# electrovanne.net
KiCad netlist of a schematic drawn in EAGLE
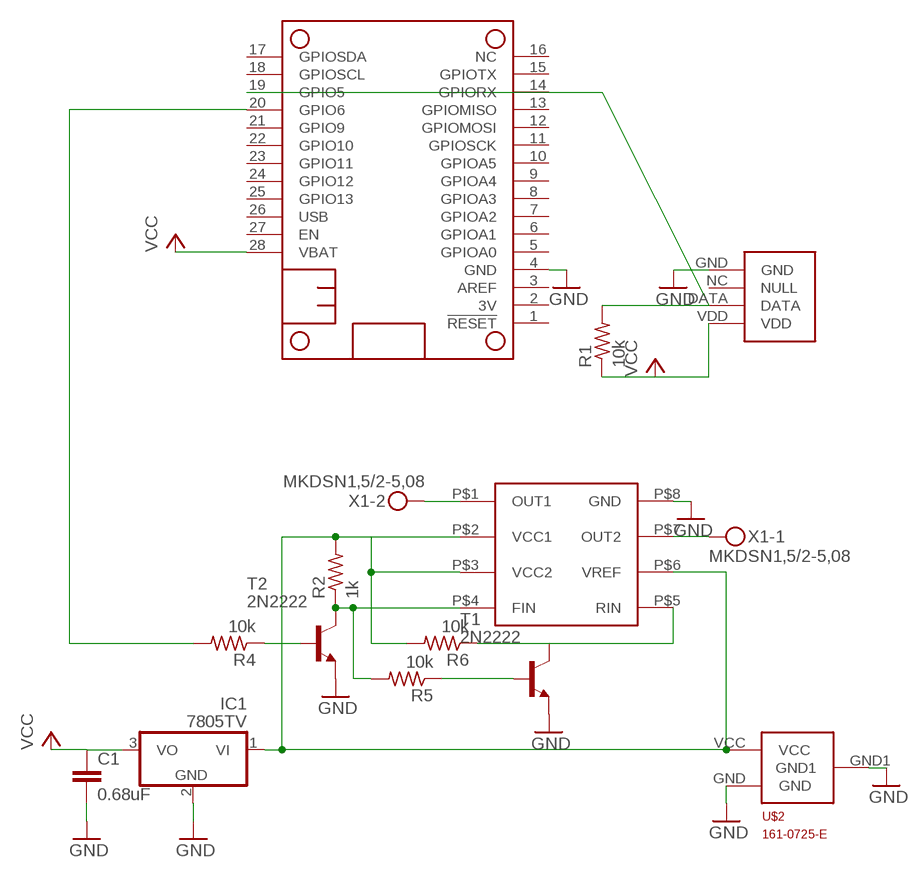
[diagram p0: schematic, sheet 1]

(export (version "E")
  (design (tool "Eeschema 10.0.6"))
  (components
    (comp (ref "C1")
      (value "0.68uF")
      (footprint "eagle-import:0603-CAP")
      (libsource (lib "eagle-import") (part "CAP0603-CAP"))
    )
    (comp (ref "IC1")
      (value "7805TV")
      (footprint "eagle-import:TO220V")
      (libsource (lib "eagle-import") (part "78TV05"))
    )
    (comp (ref "MS1")
      (value "FEATHERWING_NODIM")
      (footprint "eagle-import:FEATHERWING_DIM")
      (libsource (lib "eagle-import") (part "FEATHERWING_NODIM"))
    )
    (comp (ref "R1")
      (value "10k")
      (footprint "eagle-import:R0603")
      (libsource (lib "eagle-import") (part "R-US_R0603"))
    )
    (comp (ref "R2")
      (value "1k")
      (footprint "eagle-import:R0603")
      (libsource (lib "eagle-import") (part "R-US_R0603"))
    )
    (comp (ref "R4")
      (value "10k")
      (footprint "eagle-import:R0603")
      (libsource (lib "eagle-import") (part "R-US_R0603"))
    )
    (comp (ref "R5")
      (value "10k")
      (footprint "eagle-import:R0603")
      (libsource (lib "eagle-import") (part "R-US_R0603"))
    )
    (comp (ref "R6")
      (value "10k")
      (footprint "eagle-import:R0603")
      (libsource (lib "eagle-import") (part "R-US_R0603"))
    )
    (comp (ref "T1")
      (value "2N2222")
      (footprint "eagle-import:TO18")
      (libsource (lib "eagle-import") (part "2N2222"))
    )
    (comp (ref "T2")
      (value "2N2222")
      (footprint "eagle-import:TO18")
      (libsource (lib "eagle-import") (part "2N2222"))
    )
    (comp (ref "U$1")
      (value "DHT22")
      (footprint "eagle-import:DHT22")
      (libsource (lib "eagle-import") (part "DHT22"))
    )
    (comp (ref "U$2")
      (value "161-0725-E")
      (footprint "eagle-import:161-0725-E")
      (libsource (lib "eagle-import") (part "161-0725-E"))
    )
    (comp (ref "U$4")
      (value "755-BD6211F-E2")
      (footprint "eagle-import:755-BD6211F-E2_DIM")
      (libsource (lib "eagle-import") (part "755-BD6211F-E2"))
    )
    (comp (ref "X1")
      (value "MKDSN1,5/2-5,08")
      (footprint "eagle-import:MKDSN1,5_2-5,08")
      (libsource (lib "eagle-import") (part "MKDSN1,5/2-5,08"))
    )
  )
  (nets
    (net (code "1") (name "/3V") (class "Default")
      (node (ref "MS1") (pin "2") (pinfunction "3V_2") (pintype "power_in"))
    )
    (net (code "2") (name "/USB") (class "Default")
      (node (ref "MS1") (pin "26") (pinfunction "USB_26") (pintype "power_in"))
    )
    (net (code "3") (name "GND") (class "Default")
      (node (ref "C1") (pin "2") (pinfunction "2_2") (pintype "passive"))
      (node (ref "IC1") (pin "2") (pinfunction "GND_2") (pintype "passive"))
      (node (ref "MS1") (pin "4") (pinfunction "GND_4") (pintype "power_in"))
      (node (ref "T1") (pin "1") (pinfunction "E_1") (pintype "passive"))
      (node (ref "T2") (pin "1") (pinfunction "E_1") (pintype "passive"))
      (node (ref "U$1") (pin "GND") (pinfunction "GND_GND") (pintype "power_in"))
      (node (ref "U$2") (pin "GND") (pinfunction "GND_GND") (pintype "bidirectional"))
      (node (ref "U$2") (pin "GND1") (pinfunction "GND1_GND1") (pintype "bidirectional"))
      (node (ref "U$4") (pin "P$8") (pinfunction "GND_P$8") (pintype "bidirectional"))
    )
    (net (code "4") (name "Net-(IC1-VI)") (class "Default")
      (node (ref "IC1") (pin "1") (pinfunction "VI_1") (pintype "input"))
      (node (ref "R2") (pin "2") (pinfunction "2_2") (pintype "passive"))
      (node (ref "R6") (pin "2") (pinfunction "2_2") (pintype "passive"))
      (node (ref "U$2") (pin "VCC") (pinfunction "VCC_VCC") (pintype "bidirectional"))
      (node (ref "U$4") (pin "P$2") (pinfunction "VCC1_P$2") (pintype "bidirectional"))
      (node (ref "U$4") (pin "P$3") (pinfunction "VCC2_P$3") (pintype "bidirectional"))
      (node (ref "U$4") (pin "P$6") (pinfunction "VREF_P$6") (pintype "bidirectional"))
    )
    (net (code "5") (name "Net-(MS1-GPIO5)") (class "Default")
      (node (ref "MS1") (pin "19") (pinfunction "GPIO5_19") (pintype "bidirectional"))
      (node (ref "R1") (pin "2") (pinfunction "2_2") (pintype "passive"))
      (node (ref "U$1") (pin "DATA") (pinfunction "DATA_DATA") (pintype "output"))
    )
    (net (code "6") (name "Net-(MS1-GPIO6)") (class "Default")
      (node (ref "MS1") (pin "20") (pinfunction "GPIO6_20") (pintype "bidirectional"))
      (node (ref "R4") (pin "2") (pinfunction "2_2") (pintype "passive"))
    )
    (net (code "7") (name "Net-(T1-B)") (class "Default")
      (node (ref "R5") (pin "1") (pinfunction "1_1") (pintype "passive"))
      (node (ref "T1") (pin "2") (pinfunction "B_2") (pintype "passive"))
    )
    (net (code "8") (name "Net-(T1-C)") (class "Default")
      (node (ref "R6") (pin "1") (pinfunction "1_1") (pintype "passive"))
      (node (ref "T1") (pin "3") (pinfunction "C_3") (pintype "passive"))
      (node (ref "U$4") (pin "P$5") (pinfunction "RIN_P$5") (pintype "bidirectional"))
    )
    (net (code "9") (name "Net-(T2-B)") (class "Default")
      (node (ref "R4") (pin "1") (pinfunction "1_1") (pintype "passive"))
      (node (ref "T2") (pin "2") (pinfunction "B_2") (pintype "passive"))
    )
    (net (code "10") (name "Net-(T2-C)") (class "Default")
      (node (ref "R2") (pin "1") (pinfunction "1_1") (pintype "passive"))
      (node (ref "R5") (pin "2") (pinfunction "2_2") (pintype "passive"))
      (node (ref "T2") (pin "3") (pinfunction "C_3") (pintype "passive"))
      (node (ref "U$4") (pin "P$4") (pinfunction "FIN_P$4") (pintype "bidirectional"))
    )
    (net (code "11") (name "Net-(U$4-OUT1)") (class "Default")
      (node (ref "U$4") (pin "P$1") (pinfunction "OUT1_P$1") (pintype "bidirectional"))
      (node (ref "X1") (pin "2") (pinfunction "KL_2") (pintype "passive"))
    )
    (net (code "12") (name "Net-(U$4-OUT2)") (class "Default")
      (node (ref "U$4") (pin "P$7") (pinfunction "OUT2_P$7") (pintype "bidirectional"))
      (node (ref "X1") (pin "1") (pinfunction "KL_1") (pintype "passive"))
    )
    (net (code "13") (name "VCC") (class "Default")
      (node (ref "C1") (pin "1") (pinfunction "1_1") (pintype "passive"))
      (node (ref "IC1") (pin "3") (pinfunction "VO_3") (pintype "passive"))
      (node (ref "MS1") (pin "28") (pinfunction "VBAT_28") (pintype "power_in"))
      (node (ref "R1") (pin "1") (pinfunction "1_1") (pintype "passive"))
      (node (ref "U$1") (pin "VDD") (pinfunction "VDD_VDD") (pintype "power_in"))
    )
    (net (code "14") (name "unconnected-(MS1-AREF-Pad3)") (class "Default")
      (node (ref "MS1") (pin "3") (pinfunction "AREF_3") (pintype "passive"))
    )
    (net (code "15") (name "unconnected-(MS1-EN-Pad27)") (class "Default")
      (node (ref "MS1") (pin "27") (pinfunction "EN_27") (pintype "passive"))
    )
    (net (code "16") (name "unconnected-(MS1-GPIO9-Pad21)") (class "Default")
      (node (ref "MS1") (pin "21") (pinfunction "GPIO9_21") (pintype "bidirectional"))
    )
    (net (code "17") (name "unconnected-(MS1-GPIO10-Pad22)") (class "Default")
      (node (ref "MS1") (pin "22") (pinfunction "GPIO10_22") (pintype "bidirectional"))
    )
    (net (code "18") (name "unconnected-(MS1-GPIO11-Pad23)") (class "Default")
      (node (ref "MS1") (pin "23") (pinfunction "GPIO11_23") (pintype "bidirectional"))
    )
    (net (code "19") (name "unconnected-(MS1-GPIO12-Pad24)") (class "Default")
      (node (ref "MS1") (pin "24") (pinfunction "GPIO12_24") (pintype "bidirectional"))
    )
    (net (code "20") (name "unconnected-(MS1-GPIO13-Pad25)") (class "Default")
      (node (ref "MS1") (pin "25") (pinfunction "GPIO13_25") (pintype "bidirectional"))
    )
    (net (code "21") (name "unconnected-(MS1-GPIOA0-Pad5)") (class "Default")
      (node (ref "MS1") (pin "5") (pinfunction "GPIOA0_5") (pintype "bidirectional"))
    )
    (net (code "22") (name "unconnected-(MS1-GPIOA1-Pad6)") (class "Default")
      (node (ref "MS1") (pin "6") (pinfunction "GPIOA1_6") (pintype "bidirectional"))
    )
    (net (code "23") (name "unconnected-(MS1-GPIOA2-Pad7)") (class "Default")
      (node (ref "MS1") (pin "7") (pinfunction "GPIOA2_7") (pintype "bidirectional"))
    )
    (net (code "24") (name "unconnected-(MS1-GPIOA3-Pad8)") (class "Default")
      (node (ref "MS1") (pin "8") (pinfunction "GPIOA3_8") (pintype "bidirectional"))
    )
    (net (code "25") (name "unconnected-(MS1-GPIOA4-Pad9)") (class "Default")
      (node (ref "MS1") (pin "9") (pinfunction "GPIOA4_9") (pintype "bidirectional"))
    )
    (net (code "26") (name "unconnected-(MS1-GPIOA5-Pad10)") (class "Default")
      (node (ref "MS1") (pin "10") (pinfunction "GPIOA5_10") (pintype "bidirectional"))
    )
    (net (code "27") (name "unconnected-(MS1-GPIOMISO-Pad13)") (class "Default")
      (node (ref "MS1") (pin "13") (pinfunction "GPIOMISO_13") (pintype "bidirectional"))
    )
    (net (code "28") (name "unconnected-(MS1-GPIOMOSI-Pad12)") (class "Default")
      (node (ref "MS1") (pin "12") (pinfunction "GPIOMOSI_12") (pintype "bidirectional"))
    )
    (net (code "29") (name "unconnected-(MS1-GPIORX-Pad14)") (class "Default")
      (node (ref "MS1") (pin "14") (pinfunction "GPIORX_14") (pintype "bidirectional"))
    )
    (net (code "30") (name "unconnected-(MS1-GPIOSCK-Pad11)") (class "Default")
      (node (ref "MS1") (pin "11") (pinfunction "GPIOSCK_11") (pintype "bidirectional"))
    )
    (net (code "31") (name "unconnected-(MS1-GPIOSCL-Pad18)") (class "Default")
      (node (ref "MS1") (pin "18") (pinfunction "GPIOSCL_18") (pintype "bidirectional"))
    )
    (net (code "32") (name "unconnected-(MS1-GPIOSDA-Pad17)") (class "Default")
      (node (ref "MS1") (pin "17") (pinfunction "GPIOSDA_17") (pintype "bidirectional"))
    )
    (net (code "33") (name "unconnected-(MS1-GPIOTX-Pad15)") (class "Default")
      (node (ref "MS1") (pin "15") (pinfunction "GPIOTX_15") (pintype "bidirectional"))
    )
    (net (code "34") (name "unconnected-(MS1-NC-Pad16)") (class "Default")
      (node (ref "MS1") (pin "16") (pinfunction "NC_16") (pintype "passive"))
    )
    (net (code "35") (name "unconnected-(MS1-~{RESET}-Pad1)") (class "Default")
      (node (ref "MS1") (pin "1") (pinfunction "~{RESET}_1") (pintype "input"))
    )
    (net (code "36") (name "unconnected-(U$1-NULL-PadNC)") (class "Default")
      (node (ref "U$1") (pin "NC") (pinfunction "NULL_NC") (pintype "no_connect"))
    )
  )
)
